# I2C_Interface.net
KiCad netlist of a schematic drawn in Altium Designer
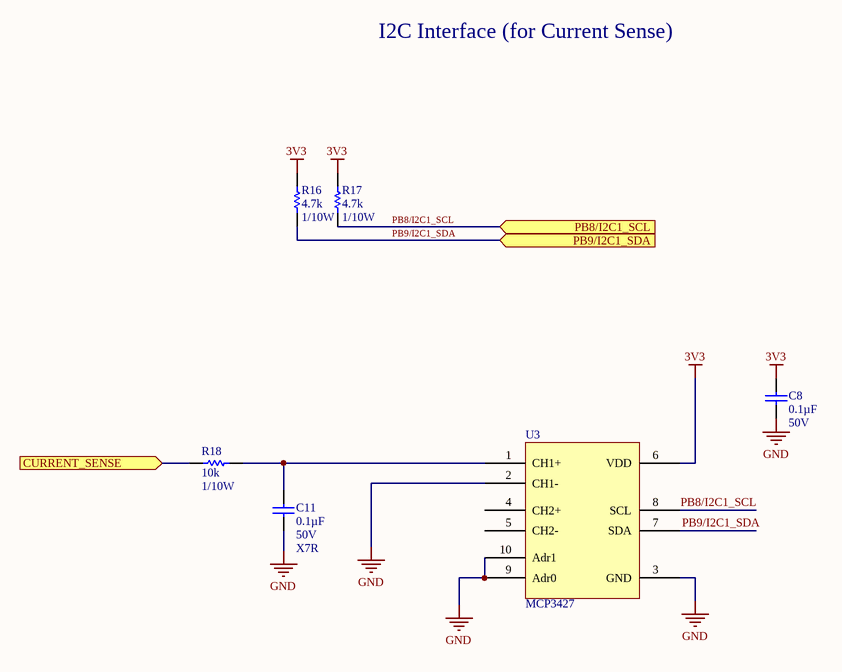
[diagram p0: I2C_Interface.SchDoc]

(export (version "E")
  (design (tool "Eeschema 10.0.6"))
  (components
    (comp (ref "C8")
      (value "CAP CER 0.1UF 50V 10% X7R 0603")
      (footprint "CAP, 0603")
      (description "0.10µF ±10% 50V Ceramic Capacitor X7R 0603 (1608 Metric)")
      (fields
        (field (name "TOLERANCE") "±10%")
        (field (name "CAPACITANCE") "0.1µF")
        (field (name "VOLTAGE") "50V")
      )
      (libsource (lib "Schematic Diagrams") (part "CAP CER 0.1UF 50V 10% X7R 0603"))
    )
    (comp (ref "C11")
      (value "CAP CER 0.1UF 50V 10% X7R 0603")
      (footprint "CAP, 0603")
      (description "0.10µF ±10% 50V Ceramic Capacitor X7R 0603 (1608 Metric)")
      (fields
        (field (name "TOLERANCE") "±10%")
        (field (name "CAPACITANCE") "0.1µF")
        (field (name "VOLTAGE") "50V")
        (field (name "TEMPERATURE COEFFICIENT") "X7R")
      )
      (libsource (lib "Schematic Diagrams") (part "CAP CER 0.1UF 50V 10% X7R 0603"))
    )
    (comp (ref "R16")
      (value "RES 4.7K OHM 1% 1/10W 0603")
      (footprint "RES, 0603")
      (description "4.7k Ohm ±1% 0.1W, 1/10W Chip Resistor 0603 (1608 Metric) Moisture Resistant Thick Film")
      (fields
        (field (name "TOLERANCE") "±1%")
        (field (name "RESISTANCE (OHMS)") "4.7k")
        (field (name "POWER (WATTS)") "1/10W")
      )
      (libsource (lib "Schematic Diagrams") (part "RES 4.7K OHM 1% 1/10W 0603"))
    )
    (comp (ref "R17")
      (value "RES 4.7K OHM 1% 1/10W 0603")
      (footprint "RES, 0603")
      (description "4.7k Ohm ±1% 0.1W, 1/10W Chip Resistor 0603 (1608 Metric) Moisture Resistant Thick Film")
      (fields
        (field (name "TOLERANCE") "±1%")
        (field (name "RESISTANCE (OHMS)") "4.7k")
        (field (name "POWER (WATTS)") "1/10W")
      )
      (libsource (lib "Schematic Diagrams") (part "RES 4.7K OHM 1% 1/10W 0603"))
    )
    (comp (ref "R18")
      (value "RES 10K OHM 1% 1/10W 0603")
      (footprint "RES, 0603")
      (description "RES SMD 10K OHM 1% 1/10W 0603")
      (fields
        (field (name "TOLERANCE") "±1%")
        (field (name "RESISTANCE") "10k")
        (field (name "POWER") "1/10W")
      )
      (libsource (lib "Schematic Diagrams") (part "RES 10K OHM 1% 1/10W 0603"))
    )
    (comp (ref "U3")
      (value "IC ADC MCP3427 10MSOP")
      (footprint "IC ADC MCP3427")
      (description "16 Bit Analog to Digital Converter 2 Input 1 Sigma-Delta 10-MSOP")
      (fields
        (field (name "MANUFACTURER") "Microchip Technology")
        (field (name "MANUFACTURER PART NUMBER") "MCP3427-E/UN")
        (field (name "BASE PART NUMBER") "MCP3427")
      )
      (libsource (lib "Schematic Diagrams") (part "IC ADC MCP3427 10MSOP"))
    )
  )
  (nets
    (net (code "1") (name "/CURRENT_SENSE") (class "Default")
      (node (ref "R18") (pin "1") (pinfunction "1_1") (pintype "passive"))
    )
    (net (code "2") (name "/PB8{slash}I2C1_SCL") (class "Default")
      (node (ref "R17") (pin "2") (pinfunction "2_2") (pintype "passive"))
      (node (ref "U3") (pin "8") (pinfunction "SCL_8") (pintype "passive"))
    )
    (net (code "3") (name "/PB9{slash}I2C1_SDA") (class "Default")
      (node (ref "R16") (pin "2") (pinfunction "2_2") (pintype "passive"))
      (node (ref "U3") (pin "7") (pinfunction "SDA_7") (pintype "passive"))
    )
    (net (code "4") (name "3V3") (class "Default")
      (node (ref "C8") (pin "1") (pinfunction "1_1") (pintype "passive"))
      (node (ref "R16") (pin "1") (pinfunction "1_1") (pintype "passive"))
      (node (ref "R17") (pin "1") (pinfunction "1_1") (pintype "passive"))
      (node (ref "U3") (pin "6") (pinfunction "VDD_6") (pintype "passive"))
    )
    (net (code "5") (name "GND") (class "Default")
      (node (ref "C11") (pin "2") (pinfunction "2_2") (pintype "passive"))
      (node (ref "C8") (pin "2") (pinfunction "2_2") (pintype "passive"))
      (node (ref "U3") (pin "10") (pinfunction "Adr1_10") (pintype "passive"))
      (node (ref "U3") (pin "2") (pinfunction "CH1-_2") (pintype "passive"))
      (node (ref "U3") (pin "3") (pinfunction "GND_3") (pintype "passive"))
      (node (ref "U3") (pin "9") (pinfunction "Adr0_9") (pintype "passive"))
    )
    (net (code "6") (name "Net-(U3-CH1+)") (class "Default")
      (node (ref "C11") (pin "1") (pinfunction "1_1") (pintype "passive"))
      (node (ref "R18") (pin "2") (pinfunction "2_2") (pintype "passive"))
      (node (ref "U3") (pin "1") (pinfunction "CH1+_1") (pintype "passive"))
    )
    (net (code "7") (name "unconnected-(U3-CH2+-Pad4)") (class "Default")
      (node (ref "U3") (pin "4") (pinfunction "CH2+_4") (pintype "passive"))
    )
    (net (code "8") (name "unconnected-(U3-CH2--Pad5)") (class "Default")
      (node (ref "U3") (pin "5") (pinfunction "CH2-_5") (pintype "passive"))
    )
  )
)
